# demoboard.net
KiCad netlist of a schematic drawn in Altium Designer
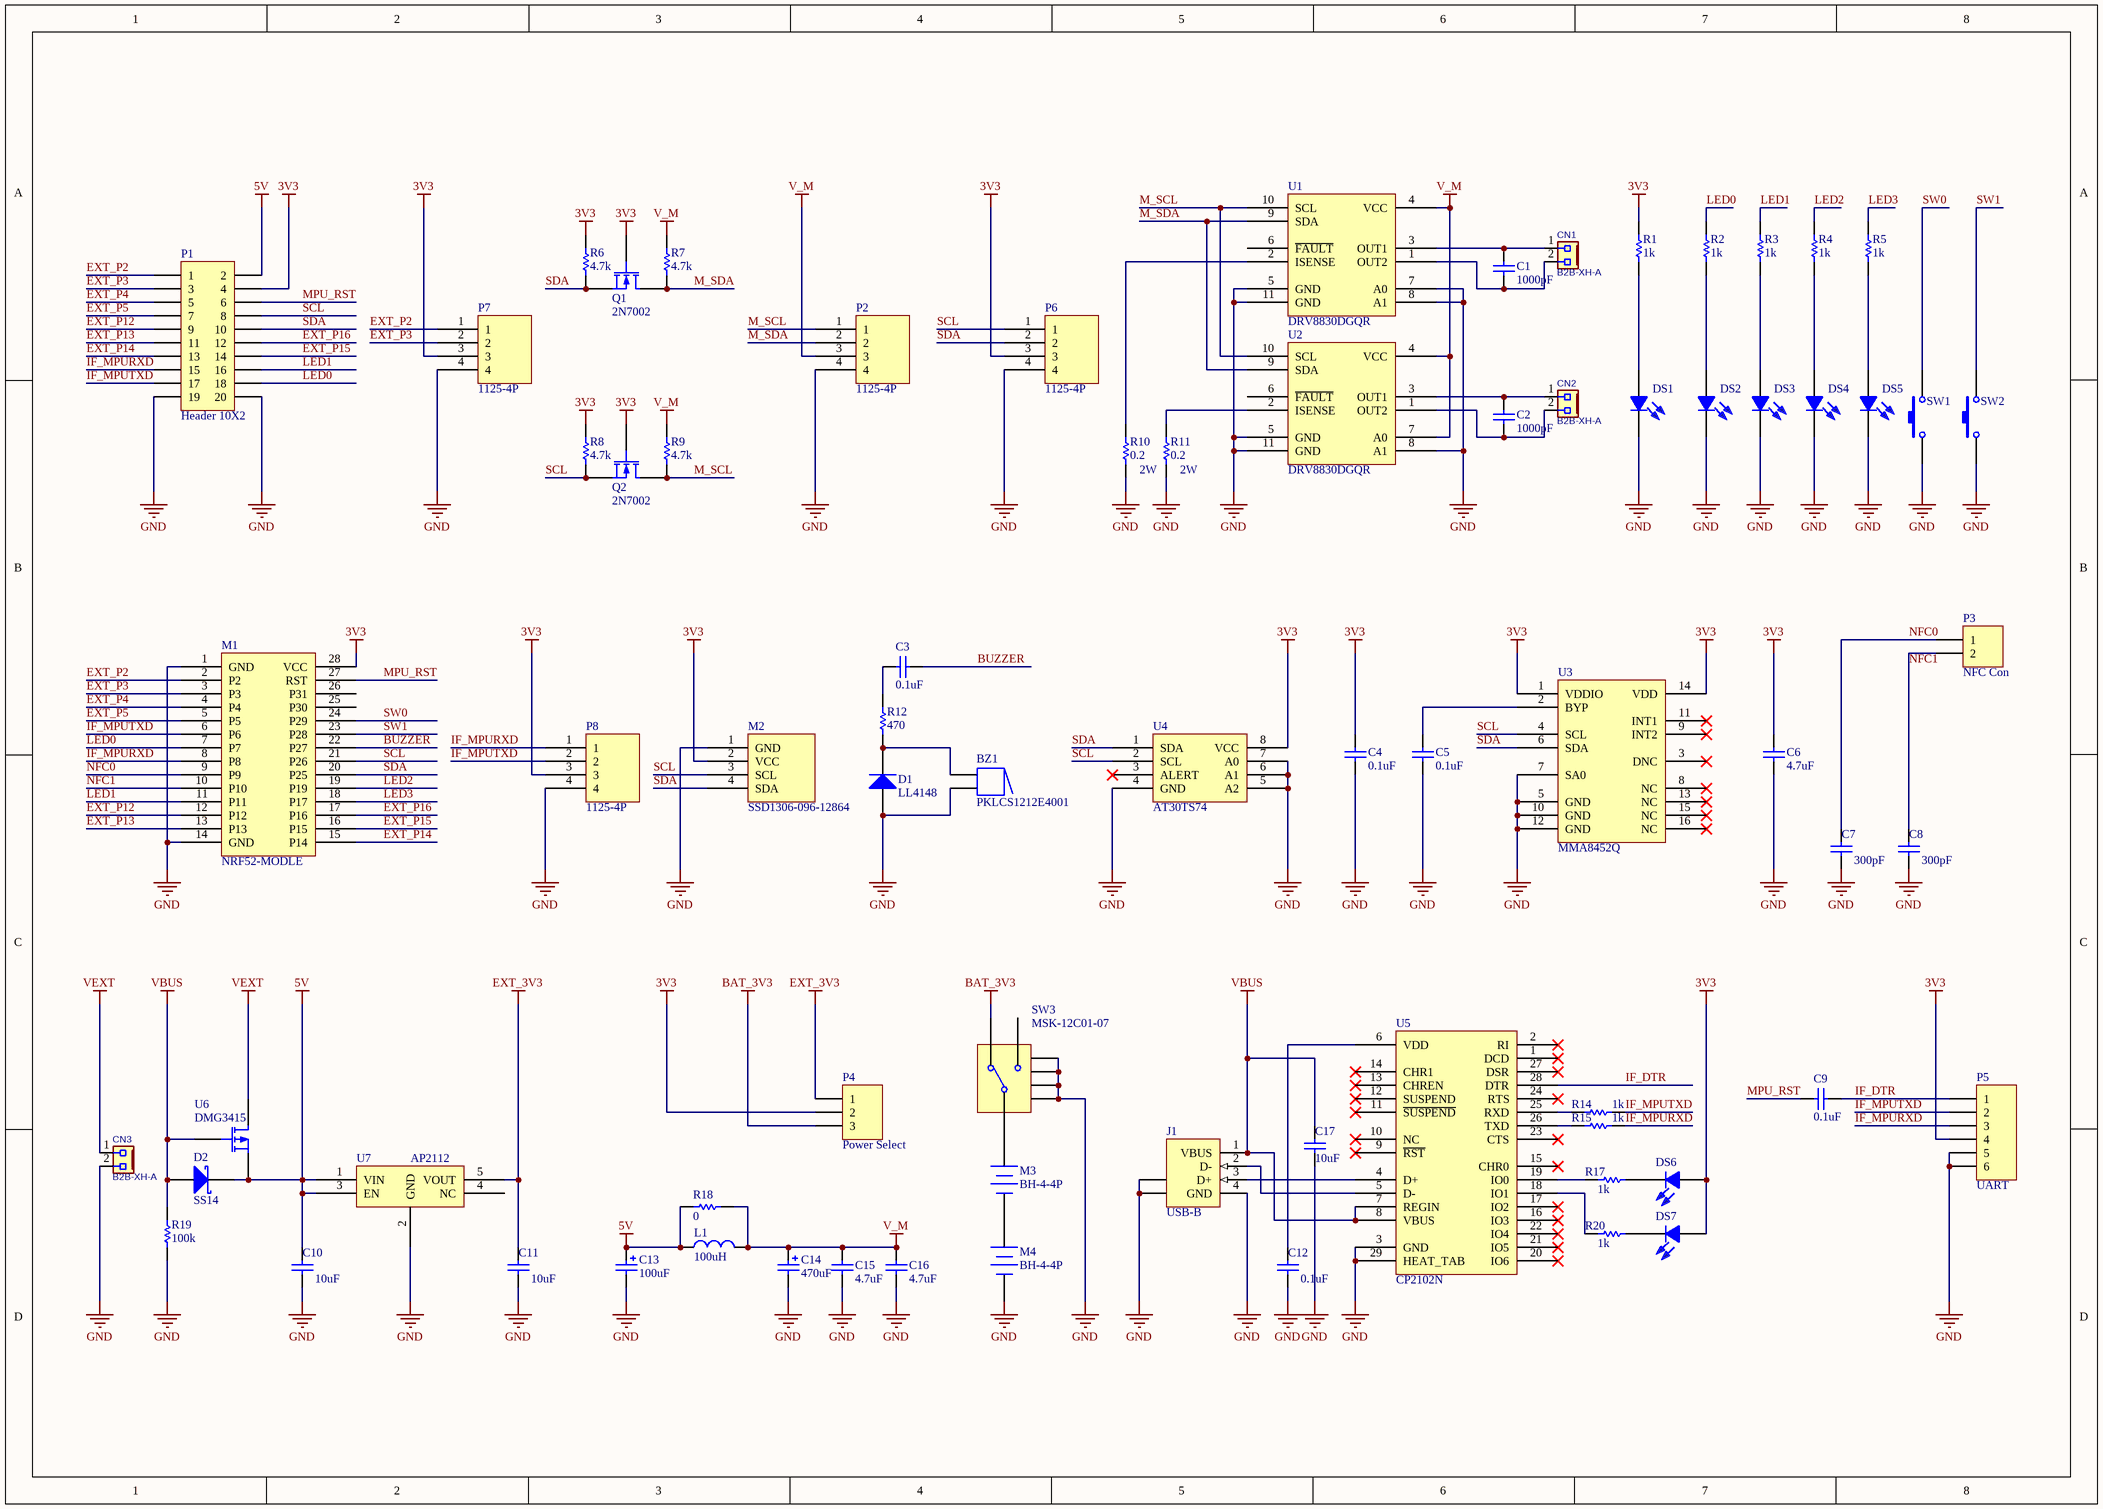
[diagram p0: demoboard.SchDoc]

(export (version "E")
  (design (tool "Eeschema 10.0.6"))
  (components
    (comp (ref "BZ1")
      (value "PKLCS1212E4001")
      (footprint "PKLCS1212E4001")
      (libsource (lib "newlib") (part "PKLCS1212E4001"))
    )
    (comp (ref "C1")
      (value "1000pF")
      (footprint "2012[0805]")
      (fields (field (name "Comment") "Cap1"))
      (libsource (lib "Other") (part "Cap1"))
    )
    (comp (ref "C2")
      (value "1000pF")
      (footprint "2012[0805]")
      (fields (field (name "Comment") "Cap1"))
      (libsource (lib "Other") (part "Cap1"))
    )
    (comp (ref "C3")
      (value "0.1uF")
      (footprint "2012[0805]")
      (fields (field (name "Comment") "Cap1"))
      (libsource (lib "Other") (part "Cap1"))
    )
    (comp (ref "C4")
      (value "0.1uF")
      (footprint "2012[0805]")
      (fields (field (name "Comment") "Cap1"))
      (libsource (lib "Other") (part "Cap1"))
    )
    (comp (ref "C5")
      (value "0.1uF")
      (footprint "2012[0805]")
      (fields (field (name "Comment") "Cap1"))
      (libsource (lib "Other") (part "Cap1"))
    )
    (comp (ref "C6")
      (value "4.7uF")
      (footprint "2012[0805]")
      (fields (field (name "Comment") "Cap1"))
      (libsource (lib "Other") (part "Cap1"))
    )
    (comp (ref "C7")
      (value "300pF")
      (footprint "2012[0805]")
      (fields (field (name "Comment") "Cap1"))
      (libsource (lib "Other") (part "Cap1"))
    )
    (comp (ref "C8")
      (value "300pF")
      (footprint "2012[0805]")
      (fields (field (name "Comment") "Cap1"))
      (libsource (lib "Other") (part "Cap1"))
    )
    (comp (ref "C9")
      (value "0.1uF")
      (footprint "2012[0805]")
      (fields (field (name "Comment") "Cap1"))
      (libsource (lib "Other") (part "Cap1"))
    )
    (comp (ref "C10")
      (value "10uF")
      (footprint "2012[0805]")
      (fields (field (name "Comment") "Cap1"))
      (libsource (lib "Other") (part "Cap1"))
    )
    (comp (ref "C11")
      (value "10uF")
      (footprint "2012[0805]")
      (fields (field (name "Comment") "Cap1"))
      (libsource (lib "Other") (part "Cap1"))
    )
    (comp (ref "C12")
      (value "0.1uF")
      (footprint "2012[0805]")
      (fields (field (name "Comment") "Cap1"))
      (libsource (lib "Other") (part "Cap1"))
    )
    (comp (ref "C13")
      (value "100uF")
      (footprint "CE04-8")
      (fields (field (name "Comment") "Cap2"))
      (libsource (lib "Other") (part "Cap2"))
    )
    (comp (ref "C14")
      (value "470uF")
      (footprint "CE04-8")
      (fields (field (name "Comment") "Cap2"))
      (libsource (lib "Other") (part "Cap2"))
    )
    (comp (ref "C15")
      (value "4.7uF")
      (footprint "2012[0805]")
      (fields (field (name "Comment") "Cap1"))
      (libsource (lib "Other") (part "Cap1"))
    )
    (comp (ref "C16")
      (value "4.7uF")
      (footprint "2012[0805]")
      (fields (field (name "Comment") "Cap1"))
      (libsource (lib "Other") (part "Cap1"))
    )
    (comp (ref "C17")
      (value "10uF")
      (footprint "2012[0805]")
      (fields (field (name "Comment") "Cap1"))
      (libsource (lib "Other") (part "Cap1"))
    )
    (comp (ref "CN1")
      (value "B2B-XH-A")
      (footprint "CND-B2B-XH-A")
      (description "XHシリーズ ベース付ポスト トップ型 2.5mmピッチ　250V 3A")
      (libsource (lib "Connector") (part "B2B-XH-A"))
    )
    (comp (ref "CN2")
      (value "B2B-XH-A")
      (footprint "CND-B2B-XH-A")
      (description "XHシリーズ ベース付ポスト トップ型 2.5mmピッチ　250V 3A")
      (libsource (lib "Connector") (part "B2B-XH-A"))
    )
    (comp (ref "CN3")
      (value "B2B-XH-A")
      (footprint "CND-B2B-XH-A")
      (description "XHシリーズ ベース付ポスト トップ型 2.5mmピッチ　250V 3A")
      (libsource (lib "Connector") (part "B2B-XH-A"))
    )
    (comp (ref "D1") (value "LL4148") (footprint "SOD80") (libsource (lib "Diode") (part "LL4148")))
    (comp (ref "D2") (value "SS14") (footprint "DO-214AC") (libsource (lib "Diode") (part "SS14")))
    (comp (ref "DS1") (value "~") (footprint "3216[1206]+A") (libsource (lib "Optical") (part "LED")))
    (comp (ref "DS2") (value "~") (footprint "3216[1206]+A") (libsource (lib "Optical") (part "LED")))
    (comp (ref "DS3") (value "~") (footprint "3216[1206]+A") (libsource (lib "Optical") (part "LED")))
    (comp (ref "DS4") (value "~") (footprint "3216[1206]+A") (libsource (lib "Optical") (part "LED")))
    (comp (ref "DS5") (value "~") (footprint "3216[1206]+A") (libsource (lib "Optical") (part "LED")))
    (comp (ref "DS6") (value "~") (footprint "3216[1206]+A") (libsource (lib "Optical") (part "LED")))
    (comp (ref "DS7") (value "~") (footprint "3216[1206]+A") (libsource (lib "Optical") (part "LED")))
    (comp (ref "J1")
      (value "USB-B")
      (footprint "USB-B-MICRO")
      (description "USB 1.1, Right Angle, Thru-Hole, B Type, Receptacle, 4 Position, White")
      (fields (field (name "PUBLISHER") "Altium Limited"))
      (libsource (lib "Connector") (part "USB-B"))
    )
    (comp (ref "L1")
      (value "100uH")
      (footprint "INDUCTOR-1212")
      (fields (field (name "Comment") "Inductor"))
      (libsource (lib "Other") (part "Inductor"))
    )
    (comp (ref "M1")
      (value "NRF52-MODLE")
      (footprint "NRF52-MODLE")
      (libsource (lib "newlib") (part "NRF52-MODLE"))
    )
    (comp (ref "M2")
      (value "SSD1306-096-12864")
      (footprint "SSD1306-096-12864")
      (libsource (lib "newlib") (part "SSD1306-096-12864"))
    )
    (comp (ref "M3") (value "BH-4-4P") (footprint "BH-4-4P") (libsource (lib "newlib") (part "BH-4-4P")))
    (comp (ref "M4") (value "BH-4-4P") (footprint "BH-4-4P") (libsource (lib "newlib") (part "BH-4-4P")))
    (comp (ref "P1")
      (value "Header 10X2")
      (footprint "HDR2X10")
      (description "Header, 10-Pin, Dual row")
      (fields (field (name "PUBLISHER") "Altium Limited"))
      (libsource (lib "Connector") (part "Header 10X2"))
    )
    (comp (ref "P2")
      (value "1125-4P")
      (footprint "1125-4P")
      (description "Seed Studio Grobe connector")
      (libsource (lib "newlib") (part "1125-4P"))
    )
    (comp (ref "P3")
      (value "NFC Con")
      (footprint "HDR1X2")
      (description "Header, 2-Pin")
      (fields (field (name "PUBLISHER") "Altium Limited"))
      (libsource (lib "Connector") (part "Header 2"))
    )
    (comp (ref "P4")
      (value "Power Select")
      (footprint "HDR1X3")
      (description "Header, 3-Pin")
      (fields (field (name "PUBLISHER") "Altium Limited"))
      (libsource (lib "Connector") (part "Header 3"))
    )
    (comp (ref "P5")
      (value "UART")
      (footprint "HDR1X6")
      (description "Header, 6-Pin")
      (fields (field (name "PUBLISHER") "Altium Limited"))
      (libsource (lib "Connector") (part "Header 6"))
    )
    (comp (ref "P6")
      (value "1125-4P")
      (footprint "1125-4P")
      (description "Seed Studio Grobe connector")
      (libsource (lib "newlib") (part "1125-4P"))
    )
    (comp (ref "P7")
      (value "1125-4P")
      (footprint "1125-4P")
      (description "Seed Studio Grobe connector")
      (libsource (lib "newlib") (part "1125-4P"))
    )
    (comp (ref "P8")
      (value "1125-4P")
      (footprint "1125-4P")
      (description "Seed Studio Grobe connector")
      (libsource (lib "newlib") (part "1125-4P"))
    )
    (comp (ref "Q1")
      (value "2N7002")
      (footprint "SOT23-3")
      (description "N-Channel MOSFET")
      (libsource (lib "Transistor") (part "2N7002"))
    )
    (comp (ref "Q2")
      (value "2N7002")
      (footprint "SOT23-3")
      (description "N-Channel MOSFET")
      (libsource (lib "Transistor") (part "2N7002"))
    )
    (comp (ref "R1")
      (value "1k")
      (footprint "2012[0805]")
      (fields (field (name "Comment") "Res"))
      (libsource (lib "Other") (part "Res"))
    )
    (comp (ref "R2")
      (value "1k")
      (footprint "2012[0805]")
      (fields (field (name "Comment") "Res"))
      (libsource (lib "Other") (part "Res"))
    )
    (comp (ref "R3")
      (value "1k")
      (footprint "2012[0805]")
      (fields (field (name "Comment") "Res"))
      (libsource (lib "Other") (part "Res"))
    )
    (comp (ref "R4")
      (value "1k")
      (footprint "2012[0805]")
      (fields (field (name "Comment") "Res"))
      (libsource (lib "Other") (part "Res"))
    )
    (comp (ref "R5")
      (value "1k")
      (footprint "2012[0805]")
      (fields (field (name "Comment") "Res"))
      (libsource (lib "Other") (part "Res"))
    )
    (comp (ref "R6")
      (value "4.7k")
      (footprint "2012[0805]")
      (fields (field (name "Comment") "Res"))
      (libsource (lib "Other") (part "Res"))
    )
    (comp (ref "R7")
      (value "4.7k")
      (footprint "2012[0805]")
      (fields (field (name "Comment") "Res"))
      (libsource (lib "Other") (part "Res"))
    )
    (comp (ref "R8")
      (value "4.7k")
      (footprint "2012[0805]")
      (fields (field (name "Comment") "Res"))
      (libsource (lib "Other") (part "Res"))
    )
    (comp (ref "R9")
      (value "4.7k")
      (footprint "2012[0805]")
      (fields (field (name "Comment") "Res"))
      (libsource (lib "Other") (part "Res"))
    )
    (comp (ref "R10")
      (value "0.2")
      (footprint "6332[2512]")
      (fields (field (name "ALTIUM_UNNAMED_1") "2W") (field (name "Comment") "Res"))
      (libsource (lib "Other") (part "Res"))
    )
    (comp (ref "R11")
      (value "0.2")
      (footprint "6332[2512]")
      (fields (field (name "ALTIUM_UNNAMED_1") "2W") (field (name "Comment") "Res"))
      (libsource (lib "Other") (part "Res"))
    )
    (comp (ref "R12")
      (value "470")
      (footprint "2012[0805]")
      (fields (field (name "Comment") "Res"))
      (libsource (lib "Other") (part "Res"))
    )
    (comp (ref "R14")
      (value "1k")
      (footprint "2012[0805]")
      (fields (field (name "Comment") "Res"))
      (libsource (lib "Other") (part "Res"))
    )
    (comp (ref "R15")
      (value "1k")
      (footprint "2012[0805]")
      (fields (field (name "Comment") "Res"))
      (libsource (lib "Other") (part "Res"))
    )
    (comp (ref "R17")
      (value "1k")
      (footprint "2012[0805]")
      (fields (field (name "Comment") "Res"))
      (libsource (lib "Other") (part "Res"))
    )
    (comp (ref "R18")
      (value "0")
      (footprint "2012[0805]")
      (fields (field (name "Comment") "Res"))
      (libsource (lib "Other") (part "Res"))
    )
    (comp (ref "R19")
      (value "100k")
      (footprint "2012[0805]")
      (fields (field (name "Comment") "Res"))
      (libsource (lib "Other") (part "Res"))
    )
    (comp (ref "R20")
      (value "1k")
      (footprint "2012[0805]")
      (fields (field (name "Comment") "Res"))
      (libsource (lib "Other") (part "Res"))
    )
    (comp (ref "SW1")
      (value "TL3342F160QG")
      (footprint "TL3342F160QG")
      (libsource (lib "Switch") (part "TL3342F160QG"))
    )
    (comp (ref "SW2")
      (value "TL3342F160QG")
      (footprint "TL3342F160QG")
      (libsource (lib "Switch") (part "TL3342F160QG"))
    )
    (comp (ref "SW3")
      (value "MSK-12C01-07")
      (footprint "MSK-12C01-07")
      (libsource (lib "Switch") (part "MSK-12C01-07"))
    )
    (comp (ref "U1")
      (value "DRV8830DGQR")
      (footprint "MSOP10TPH")
      (libsource (lib "newlib") (part "DRV8830DGQR"))
    )
    (comp (ref "U2")
      (value "DRV8830DGQR")
      (footprint "MSOP10TPH")
      (libsource (lib "newlib") (part "DRV8830DGQR"))
    )
    (comp (ref "U3")
      (value "MMA8452Q")
      (footprint "QFN16S-0.5")
      (description "MMA8452AQ")
      (libsource (lib "newlib") (part "MMA8452Q"))
    )
    (comp (ref "U4") (value "AT30TS74") (footprint "SOIC8") (libsource (lib "newlib") (part "AT30TS74")))
    (comp (ref "U5")
      (value "CP2102N")
      (footprint "QFN28-0.5")
      (fields (field (name "PART NUMBER") "CP2102"))
      (libsource (lib "newlib") (part "CP2102N"))
    )
    (comp (ref "U6")
      (value "DMG3415")
      (footprint "SOT23-3")
      (fields (field (name "PUBLISHER") "Altium Limited"))
      (libsource (lib "newlib") (part "DMG3415"))
    )
    (comp (ref "U7") (value "AP2112") (footprint "SOT23-5") (libsource (lib "newlib") (part "AP2112")))
  )
  (nets
    (net (code "1") (name "/BUZZER") (class "Default")
      (node (ref "C3") (pin "2") (pinfunction "2_2") (pintype "passive"))
      (node (ref "M1") (pin "22") (pinfunction "P27_22") (pintype "passive"))
    )
    (net (code "2") (name "/EXT_P2") (class "Default")
      (node (ref "M1") (pin "2") (pinfunction "P2_2") (pintype "passive"))
      (node (ref "P1") (pin "1") (pinfunction "1_1") (pintype "passive"))
      (node (ref "P7") (pin "1") (pinfunction "1_1") (pintype "passive"))
    )
    (net (code "3") (name "/EXT_P3") (class "Default")
      (node (ref "M1") (pin "3") (pinfunction "P3_3") (pintype "passive"))
      (node (ref "P1") (pin "3") (pinfunction "3_3") (pintype "passive"))
      (node (ref "P7") (pin "2") (pinfunction "2_2") (pintype "passive"))
    )
    (net (code "4") (name "/EXT_P4") (class "Default")
      (node (ref "M1") (pin "4") (pinfunction "P4_4") (pintype "passive"))
      (node (ref "P1") (pin "5") (pinfunction "5_5") (pintype "passive"))
    )
    (net (code "5") (name "/EXT_P5") (class "Default")
      (node (ref "M1") (pin "5") (pinfunction "P5_5") (pintype "passive"))
      (node (ref "P1") (pin "7") (pinfunction "7_7") (pintype "passive"))
    )
    (net (code "6") (name "/EXT_P12") (class "Default")
      (node (ref "M1") (pin "12") (pinfunction "P12_12") (pintype "passive"))
      (node (ref "P1") (pin "9") (pinfunction "9_9") (pintype "passive"))
    )
    (net (code "7") (name "/EXT_P13") (class "Default")
      (node (ref "M1") (pin "13") (pinfunction "P13_13") (pintype "passive"))
      (node (ref "P1") (pin "11") (pinfunction "11_11") (pintype "passive"))
    )
    (net (code "8") (name "/EXT_P14") (class "Default")
      (node (ref "M1") (pin "15") (pinfunction "P14_15") (pintype "passive"))
      (node (ref "P1") (pin "13") (pinfunction "13_13") (pintype "passive"))
    )
    (net (code "9") (name "/EXT_P15") (class "Default")
      (node (ref "M1") (pin "16") (pinfunction "P15_16") (pintype "passive"))
      (node (ref "P1") (pin "14") (pinfunction "14_14") (pintype "passive"))
    )
    (net (code "10") (name "/EXT_P16") (class "Default")
      (node (ref "M1") (pin "17") (pinfunction "P16_17") (pintype "passive"))
      (node (ref "P1") (pin "12") (pinfunction "12_12") (pintype "passive"))
    )
    (net (code "11") (name "/IF_DTR") (class "Default")
      (node (ref "C9") (pin "1") (pinfunction "1_1") (pintype "passive"))
      (node (ref "P5") (pin "1") (pinfunction "1_1") (pintype "passive"))
      (node (ref "U5") (pin "28") (pinfunction "DTR_28") (pintype "passive"))
    )
    (net (code "12") (name "/IF_MPURXD") (class "Default")
      (node (ref "M1") (pin "8") (pinfunction "P8_8") (pintype "passive"))
      (node (ref "P1") (pin "15") (pinfunction "15_15") (pintype "passive"))
      (node (ref "P5") (pin "3") (pinfunction "3_3") (pintype "passive"))
      (node (ref "P8") (pin "1") (pinfunction "1_1") (pintype "passive"))
      (node (ref "R15") (pin "2") (pinfunction "2_2") (pintype "passive"))
    )
    (net (code "13") (name "/IF_MPUTXD") (class "Default")
      (node (ref "M1") (pin "6") (pinfunction "P6_6") (pintype "passive"))
      (node (ref "P1") (pin "17") (pinfunction "17_17") (pintype "passive"))
      (node (ref "P5") (pin "2") (pinfunction "2_2") (pintype "passive"))
      (node (ref "P8") (pin "2") (pinfunction "2_2") (pintype "passive"))
      (node (ref "R14") (pin "2") (pinfunction "2_2") (pintype "passive"))
    )
    (net (code "14") (name "/LED0") (class "Default")
      (node (ref "M1") (pin "7") (pinfunction "P7_7") (pintype "passive"))
      (node (ref "P1") (pin "18") (pinfunction "18_18") (pintype "passive"))
      (node (ref "R2") (pin "1") (pinfunction "1_1") (pintype "passive"))
    )
    (net (code "15") (name "/LED1") (class "Default")
      (node (ref "M1") (pin "11") (pinfunction "P11_11") (pintype "passive"))
      (node (ref "P1") (pin "16") (pinfunction "16_16") (pintype "passive"))
      (node (ref "R3") (pin "1") (pinfunction "1_1") (pintype "passive"))
    )
    (net (code "16") (name "/LED2") (class "Default")
      (node (ref "M1") (pin "19") (pinfunction "P19_19") (pintype "passive"))
      (node (ref "R4") (pin "1") (pinfunction "1_1") (pintype "passive"))
    )
    (net (code "17") (name "/LED3") (class "Default")
      (node (ref "M1") (pin "18") (pinfunction "P17_18") (pintype "passive"))
      (node (ref "R5") (pin "1") (pinfunction "1_1") (pintype "passive"))
    )
    (net (code "18") (name "/MPU_RST") (class "Default")
      (node (ref "C9") (pin "2") (pinfunction "2_2") (pintype "passive"))
      (node (ref "M1") (pin "27") (pinfunction "RST_27") (pintype "passive"))
      (node (ref "P1") (pin "6") (pinfunction "6_6") (pintype "passive"))
    )
    (net (code "19") (name "/M_SCL") (class "Default")
      (node (ref "P2") (pin "1") (pinfunction "1_1") (pintype "passive"))
      (node (ref "Q2") (pin "3") (pinfunction "D_3") (pintype "passive"))
      (node (ref "R9") (pin "1") (pinfunction "1_1") (pintype "passive"))
      (node (ref "U1") (pin "10") (pinfunction "SCL_10") (pintype "passive"))
      (node (ref "U2") (pin "10") (pinfunction "SCL_10") (pintype "passive"))
    )
    (net (code "20") (name "/M_SDA") (class "Default")
      (node (ref "P2") (pin "2") (pinfunction "2_2") (pintype "passive"))
      (node (ref "Q1") (pin "3") (pinfunction "D_3") (pintype "passive"))
      (node (ref "R7") (pin "1") (pinfunction "1_1") (pintype "passive"))
      (node (ref "U1") (pin "9") (pinfunction "SDA_9") (pintype "passive"))
      (node (ref "U2") (pin "9") (pinfunction "SDA_9") (pintype "passive"))
    )
    (net (code "21") (name "/NFC0") (class "Default")
      (node (ref "C7") (pin "2") (pinfunction "2_2") (pintype "passive"))
      (node (ref "M1") (pin "9") (pinfunction "P9_9") (pintype "passive"))
      (node (ref "P3") (pin "1") (pinfunction "1_1") (pintype "passive"))
    )
    (net (code "22") (name "/NFC1") (class "Default")
      (node (ref "C8") (pin "2") (pinfunction "2_2") (pintype "passive"))
      (node (ref "M1") (pin "10") (pinfunction "P10_10") (pintype "passive"))
      (node (ref "P3") (pin "2") (pinfunction "2_2") (pintype "passive"))
    )
    (net (code "23") (name "/SCL") (class "Default")
      (node (ref "M1") (pin "21") (pinfunction "P26_21") (pintype "passive"))
      (node (ref "M2") (pin "3") (pinfunction "SCL_3") (pintype "passive"))
      (node (ref "P1") (pin "8") (pinfunction "8_8") (pintype "passive"))
      (node (ref "P6") (pin "1") (pinfunction "1_1") (pintype "passive"))
      (node (ref "Q2") (pin "2") (pinfunction "S_2") (pintype "passive"))
      (node (ref "R8") (pin "2") (pinfunction "2_2") (pintype "passive"))
      (node (ref "U3") (pin "4") (pinfunction "SCL_4") (pintype "passive"))
      (node (ref "U4") (pin "2") (pinfunction "SCL_2") (pintype "passive"))
    )
    (net (code "24") (name "/SDA") (class "Default")
      (node (ref "M1") (pin "20") (pinfunction "P25_20") (pintype "passive"))
      (node (ref "M2") (pin "4") (pinfunction "SDA_4") (pintype "passive"))
      (node (ref "P1") (pin "10") (pinfunction "10_10") (pintype "passive"))
      (node (ref "P6") (pin "2") (pinfunction "2_2") (pintype "passive"))
      (node (ref "Q1") (pin "2") (pinfunction "S_2") (pintype "passive"))
      (node (ref "R6") (pin "2") (pinfunction "2_2") (pintype "passive"))
      (node (ref "U3") (pin "6") (pinfunction "SDA_6") (pintype "passive"))
      (node (ref "U4") (pin "1") (pinfunction "SDA_1") (pintype "passive"))
    )
    (net (code "25") (name "/SW0") (class "Default")
      (node (ref "M1") (pin "24") (pinfunction "P29_24") (pintype "passive"))
      (node (ref "SW1") (pin "3") (pinfunction "3_3") (pintype "passive"))
    )
    (net (code "26") (name "/SW1") (class "Default")
      (node (ref "M1") (pin "23") (pinfunction "P28_23") (pintype "passive"))
      (node (ref "SW2") (pin "3") (pinfunction "3_3") (pintype "passive"))
    )
    (net (code "27") (name "3V3") (class "Default")
      (node (ref "C4") (pin "1") (pinfunction "1_1") (pintype "passive"))
      (node (ref "C6") (pin "1") (pinfunction "1_1") (pintype "passive"))
      (node (ref "DS6") (pin "1") (pintype "passive"))
      (node (ref "DS7") (pin "1") (pintype "passive"))
      (node (ref "M1") (pin "28") (pinfunction "VCC_28") (pintype "passive"))
      (node (ref "M2") (pin "2") (pinfunction "VCC_2") (pintype "passive"))
      (node (ref "P1") (pin "4") (pinfunction "4_4") (pintype "passive"))
      (node (ref "P4") (pin "2") (pinfunction "2_2") (pintype "passive"))
      (node (ref "P5") (pin "4") (pinfunction "4_4") (pintype "passive"))
      (node (ref "P6") (pin "3") (pinfunction "3_3") (pintype "passive"))
      (node (ref "P7") (pin "3") (pinfunction "3_3") (pintype "passive"))
      (node (ref "P8") (pin "3") (pinfunction "3_3") (pintype "passive"))
      (node (ref "Q1") (pin "1") (pinfunction "G_1") (pintype "passive"))
      (node (ref "Q2") (pin "1") (pinfunction "G_1") (pintype "passive"))
      (node (ref "R1") (pin "1") (pinfunction "1_1") (pintype "passive"))
      (node (ref "R6") (pin "1") (pinfunction "1_1") (pintype "passive"))
      (node (ref "R8") (pin "1") (pinfunction "1_1") (pintype "passive"))
      (node (ref "U3") (pin "1") (pinfunction "VDDIO_1") (pintype "passive"))
      (node (ref "U3") (pin "14") (pinfunction "VDD_14") (pintype "passive"))
      (node (ref "U4") (pin "8") (pinfunction "VCC_8") (pintype "passive"))
    )
    (net (code "28") (name "5V") (class "Default")
      (node (ref "C10") (pin "2") (pinfunction "2_2") (pintype "passive"))
      (node (ref "C13") (pin "1") (pinfunction "1_1") (pintype "passive"))
      (node (ref "D2") (pin "2") (pinfunction "K_2") (pintype "passive"))
      (node (ref "L1") (pin "1") (pinfunction "1_1") (pintype "passive"))
      (node (ref "P1") (pin "2") (pinfunction "2_2") (pintype "passive"))
      (node (ref "R18") (pin "1") (pinfunction "1_1") (pintype "passive"))
      (node (ref "U6") (pin "2") (pinfunction "S_2") (pintype "passive"))
      (node (ref "U7") (pin "1") (pinfunction "VIN_1") (pintype "passive"))
      (node (ref "U7") (pin "3") (pinfunction "EN_3") (pintype "passive"))
    )
    (net (code "29") (name "BAT_3V3") (class "Default")
      (node (ref "P4") (pin "3") (pinfunction "3_3") (pintype "passive"))
      (node (ref "SW3") (pin "1") (pinfunction "1_1") (pintype "passive"))
    )
    (net (code "30") (name "EXT_3V3") (class "Default")
      (node (ref "C11") (pin "2") (pinfunction "2_2") (pintype "passive"))
      (node (ref "P4") (pin "1") (pinfunction "1_1") (pintype "passive"))
      (node (ref "U7") (pin "5") (pinfunction "VOUT_5") (pintype "passive"))
    )
    (net (code "31") (name "GND") (class "Default")
      (node (ref "BZ1") (pin "2") (pinfunction "2_2") (pintype "passive"))
      (node (ref "C10") (pin "1") (pinfunction "1_1") (pintype "passive"))
      (node (ref "C11") (pin "1") (pinfunction "1_1") (pintype "passive"))
      (node (ref "C12") (pin "1") (pinfunction "1_1") (pintype "passive"))
      (node (ref "C13") (pin "2") (pinfunction "2_2") (pintype "passive"))
      (node (ref "C14") (pin "2") (pinfunction "2_2") (pintype "passive"))
      (node (ref "C15") (pin "2") (pinfunction "2_2") (pintype "passive"))
      (node (ref "C16") (pin "2") (pinfunction "2_2") (pintype "passive"))
      (node (ref "C17") (pin "1") (pinfunction "1_1") (pintype "passive"))
      (node (ref "C4") (pin "2") (pinfunction "2_2") (pintype "passive"))
      (node (ref "C5") (pin "2") (pinfunction "2_2") (pintype "passive"))
      (node (ref "C6") (pin "2") (pinfunction "2_2") (pintype "passive"))
      (node (ref "C7") (pin "1") (pinfunction "1_1") (pintype "passive"))
      (node (ref "C8") (pin "1") (pinfunction "1_1") (pintype "passive"))
      (node (ref "CN3") (pin "2") (pinfunction "2_2") (pintype "passive"))
      (node (ref "D1") (pin "1") (pinfunction "A_1") (pintype "passive"))
      (node (ref "DS1") (pin "2") (pintype "passive"))
      (node (ref "DS2") (pin "2") (pintype "passive"))
      (node (ref "DS3") (pin "2") (pintype "passive"))
      (node (ref "DS4") (pin "2") (pintype "passive"))
      (node (ref "DS5") (pin "2") (pintype "passive"))
      (node (ref "J1") (pin "4") (pinfunction "GND_4") (pintype "power_in"))
      (node (ref "J1") (pin "5") (pinfunction "SHLD_5") (pintype "passive"))
      (node (ref "J1") (pin "6") (pinfunction "SHLD_6") (pintype "passive"))
      (node (ref "M1") (pin "1") (pinfunction "GND_1") (pintype "passive"))
      (node (ref "M1") (pin "14") (pinfunction "GND_14") (pintype "passive"))
      (node (ref "M2") (pin "1") (pinfunction "GND_1") (pintype "passive"))
      (node (ref "M4") (pin "2") (pinfunction "-_2") (pintype "passive"))
      (node (ref "P1") (pin "19") (pinfunction "19_19") (pintype "passive"))
      (node (ref "P1") (pin "20") (pinfunction "20_20") (pintype "passive"))
      (node (ref "P2") (pin "4") (pinfunction "4_4") (pintype "passive"))
      (node (ref "P5") (pin "5") (pinfunction "5_5") (pintype "passive"))
      (node (ref "P5") (pin "6") (pinfunction "6_6") (pintype "passive"))
      (node (ref "P6") (pin "4") (pinfunction "4_4") (pintype "passive"))
      (node (ref "P7") (pin "4") (pinfunction "4_4") (pintype "passive"))
      (node (ref "P8") (pin "4") (pinfunction "4_4") (pintype "passive"))
      (node (ref "R10") (pin "1") (pinfunction "1_1") (pintype "passive"))
      (node (ref "R11") (pin "1") (pinfunction "1_1") (pintype "passive"))
      (node (ref "R19") (pin "1") (pinfunction "1_1") (pintype "passive"))
      (node (ref "SW1") (pin "1") (pinfunction "1_1") (pintype "passive"))
      (node (ref "SW2") (pin "1") (pinfunction "1_1") (pintype "passive"))
      (node (ref "SW3") (pin "4") (pinfunction "4_4") (pintype "passive"))
      (node (ref "SW3") (pin "5") (pinfunction "5_5") (pintype "passive"))
      (node (ref "SW3") (pin "6") (pinfunction "6_6") (pintype "passive"))
      (node (ref "SW3") (pin "7") (pinfunction "7_7") (pintype "passive"))
      (node (ref "U1") (pin "11") (pinfunction "GND_11") (pintype "passive"))
      (node (ref "U1") (pin "5") (pinfunction "GND_5") (pintype "passive"))
      (node (ref "U1") (pin "7") (pinfunction "A0_7") (pintype "passive"))
      (node (ref "U1") (pin "8") (pinfunction "A1_8") (pintype "passive"))
      (node (ref "U2") (pin "11") (pinfunction "GND_11") (pintype "passive"))
      (node (ref "U2") (pin "5") (pinfunction "GND_5") (pintype "passive"))
      (node (ref "U2") (pin "8") (pinfunction "A1_8") (pintype "passive"))
      (node (ref "U3") (pin "10") (pinfunction "GND_10") (pintype "passive"))
      (node (ref "U3") (pin "12") (pinfunction "GND_12") (pintype "passive"))
      (node (ref "U3") (pin "5") (pinfunction "GND_5") (pintype "passive"))
      (node (ref "U3") (pin "7") (pinfunction "SA0_7") (pintype "passive"))
      (node (ref "U4") (pin "4") (pinfunction "GND_4") (pintype "passive"))
      (node (ref "U4") (pin "5") (pinfunction "A2_5") (pintype "passive"))
      (node (ref "U4") (pin "6") (pinfunction "A1_6") (pintype "passive"))
      (node (ref "U4") (pin "7") (pinfunction "A0_7") (pintype "passive"))
      (node (ref "U5") (pin "29") (pinfunction "HEAT_TAB_29") (pintype "passive"))
      (node (ref "U5") (pin "3") (pinfunction "GND_3") (pintype "passive"))
      (node (ref "U7") (pin "2") (pinfunction "GND_2") (pintype "passive"))
    )
    (net (code "32") (name "Net-(C3-Pad1)") (class "Default")
      (node (ref "C3") (pin "1") (pinfunction "1_1") (pintype "passive"))
      (node (ref "R12") (pin "2") (pinfunction "2_2") (pintype "passive"))
    )
    (net (code "33") (name "Net-(D1-K)") (class "Default")
      (node (ref "BZ1") (pin "1") (pinfunction "1_1") (pintype "passive"))
      (node (ref "D1") (pin "2") (pinfunction "K_2") (pintype "passive"))
      (node (ref "R12") (pin "1") (pinfunction "1_1") (pintype "passive"))
    )
    (net (code "34") (name "Net-(DS1-Pad1)") (class "Default")
      (node (ref "DS1") (pin "1") (pintype "passive"))
      (node (ref "R1") (pin "2") (pinfunction "2_2") (pintype "passive"))
    )
    (net (code "35") (name "Net-(DS2-Pad1)") (class "Default")
      (node (ref "DS2") (pin "1") (pintype "passive"))
      (node (ref "R2") (pin "2") (pinfunction "2_2") (pintype "passive"))
    )
    (net (code "36") (name "Net-(DS3-Pad1)") (class "Default")
      (node (ref "DS3") (pin "1") (pintype "passive"))
      (node (ref "R3") (pin "2") (pinfunction "2_2") (pintype "passive"))
    )
    (net (code "37") (name "Net-(DS4-Pad1)") (class "Default")
      (node (ref "DS4") (pin "1") (pintype "passive"))
      (node (ref "R4") (pin "2") (pinfunction "2_2") (pintype "passive"))
    )
    (net (code "38") (name "Net-(DS5-Pad1)") (class "Default")
      (node (ref "DS5") (pin "1") (pintype "passive"))
      (node (ref "R5") (pin "2") (pinfunction "2_2") (pintype "passive"))
    )
    (net (code "39") (name "Net-(DS6-Pad2)") (class "Default")
      (node (ref "DS6") (pin "2") (pintype "passive"))
      (node (ref "R17") (pin "1") (pinfunction "1_1") (pintype "passive"))
    )
    (net (code "40") (name "Net-(DS7-Pad2)") (class "Default")
      (node (ref "DS7") (pin "2") (pintype "passive"))
      (node (ref "R20") (pin "1") (pinfunction "1_1") (pintype "passive"))
    )
    (net (code "41") (name "Net-(J1-D+)") (class "Default")
      (node (ref "J1") (pin "3") (pinfunction "D+_3") (pintype "input"))
      (node (ref "U5") (pin "4") (pinfunction "D+_4") (pintype "passive"))
    )
    (net (code "42") (name "Net-(J1-D-)") (class "Default")
      (node (ref "J1") (pin "2") (pinfunction "D-_2") (pintype "input"))
      (node (ref "U5") (pin "5") (pinfunction "D-_5") (pintype "passive"))
    )
    (net (code "43") (name "Net-(M3-+)") (class "Default")
      (node (ref "M3") (pin "1") (pinfunction "+_1") (pintype "passive"))
      (node (ref "SW3") (pin "2") (pinfunction "2_2") (pintype "passive"))
    )
    (net (code "44") (name "Net-(M3--)") (class "Default")
      (node (ref "M3") (pin "2") (pinfunction "-_2") (pintype "passive"))
      (node (ref "M4") (pin "1") (pinfunction "+_1") (pintype "passive"))
    )
    (net (code "45") (name "Net-(U1-ISENSE)") (class "Default")
      (node (ref "R10") (pin "2") (pinfunction "2_2") (pintype "passive"))
      (node (ref "U1") (pin "2") (pinfunction "ISENSE_2") (pintype "passive"))
    )
    (net (code "46") (name "Net-(U1-OUT1)") (class "Default")
      (node (ref "C1") (pin "1") (pinfunction "1_1") (pintype "passive"))
      (node (ref "CN1") (pin "1") (pinfunction "1_1") (pintype "passive"))
      (node (ref "U1") (pin "3") (pinfunction "OUT1_3") (pintype "passive"))
    )
    (net (code "47") (name "Net-(U1-OUT2)") (class "Default")
      (node (ref "C1") (pin "2") (pinfunction "2_2") (pintype "passive"))
      (node (ref "CN1") (pin "2") (pinfunction "2_2") (pintype "passive"))
      (node (ref "U1") (pin "1") (pinfunction "OUT2_1") (pintype "passive"))
    )
    (net (code "48") (name "Net-(U2-ISENSE)") (class "Default")
      (node (ref "R11") (pin "2") (pinfunction "2_2") (pintype "passive"))
      (node (ref "U2") (pin "2") (pinfunction "ISENSE_2") (pintype "passive"))
    )
    (net (code "49") (name "Net-(U2-OUT1)") (class "Default")
      (node (ref "C2") (pin "1") (pinfunction "1_1") (pintype "passive"))
      (node (ref "CN2") (pin "1") (pinfunction "1_1") (pintype "passive"))
      (node (ref "U2") (pin "3") (pinfunction "OUT1_3") (pintype "passive"))
    )
    (net (code "50") (name "Net-(U2-OUT2)") (class "Default")
      (node (ref "C2") (pin "2") (pinfunction "2_2") (pintype "passive"))
      (node (ref "CN2") (pin "2") (pinfunction "2_2") (pintype "passive"))
      (node (ref "U2") (pin "1") (pinfunction "OUT2_1") (pintype "passive"))
    )
    (net (code "51") (name "Net-(U3-BYP)") (class "Default")
      (node (ref "C5") (pin "1") (pinfunction "1_1") (pintype "passive"))
      (node (ref "U3") (pin "2") (pinfunction "BYP_2") (pintype "passive"))
    )
    (net (code "52") (name "Net-(U5-IO0)") (class "Default")
      (node (ref "R17") (pin "2") (pinfunction "2_2") (pintype "passive"))
      (node (ref "U5") (pin "19") (pinfunction "IO0_19") (pintype "passive"))
    )
    (net (code "53") (name "Net-(U5-IO1)") (class "Default")
      (node (ref "R20") (pin "2") (pinfunction "2_2") (pintype "passive"))
      (node (ref "U5") (pin "18") (pinfunction "IO1_18") (pintype "passive"))
    )
    (net (code "54") (name "Net-(U5-RXD)") (class "Default")
      (node (ref "R14") (pin "1") (pinfunction "1_1") (pintype "passive"))
      (node (ref "U5") (pin "25") (pinfunction "RXD_25") (pintype "passive"))
    )
    (net (code "55") (name "Net-(U5-TXD)") (class "Default")
      (node (ref "R15") (pin "1") (pinfunction "1_1") (pintype "passive"))
      (node (ref "U5") (pin "26") (pinfunction "TXD_26") (pintype "passive"))
    )
    (net (code "56") (name "Net-(U5-VDD)") (class "Default")
      (node (ref "C12") (pin "2") (pinfunction "2_2") (pintype "passive"))
      (node (ref "U5") (pin "6") (pinfunction "VDD_6") (pintype "passive"))
    )
    (net (code "57") (name "VBUS") (class "Default")
      (node (ref "C17") (pin "2") (pinfunction "2_2") (pintype "passive"))
      (node (ref "D2") (pin "1") (pinfunction "A_1") (pintype "passive"))
      (node (ref "J1") (pin "1") (pinfunction "VBUS_1") (pintype "power_in"))
      (node (ref "R19") (pin "2") (pinfunction "2_2") (pintype "passive"))
      (node (ref "U5") (pin "7") (pinfunction "REGIN_7") (pintype "passive"))
      (node (ref "U5") (pin "8") (pinfunction "VBUS_8") (pintype "passive"))
      (node (ref "U6") (pin "1") (pinfunction "G_1") (pintype "passive"))
    )
    (net (code "58") (name "VEXT") (class "Default")
      (node (ref "CN3") (pin "1") (pinfunction "1_1") (pintype "passive"))
      (node (ref "U6") (pin "3") (pinfunction "D_3") (pintype "passive"))
    )
    (net (code "59") (name "V_M") (class "Default")
      (node (ref "C14") (pin "1") (pinfunction "1_1") (pintype "passive"))
      (node (ref "C15") (pin "1") (pinfunction "1_1") (pintype "passive"))
      (node (ref "C16") (pin "1") (pinfunction "1_1") (pintype "passive"))
      (node (ref "L1") (pin "2") (pinfunction "2_2") (pintype "passive"))
      (node (ref "P2") (pin "3") (pinfunction "3_3") (pintype "passive"))
      (node (ref "R18") (pin "2") (pinfunction "2_2") (pintype "passive"))
      (node (ref "R7") (pin "2") (pinfunction "2_2") (pintype "passive"))
      (node (ref "R9") (pin "2") (pinfunction "2_2") (pintype "passive"))
      (node (ref "U1") (pin "4") (pinfunction "VCC_4") (pintype "passive"))
      (node (ref "U2") (pin "4") (pinfunction "VCC_4") (pintype "passive"))
      (node (ref "U2") (pin "7") (pinfunction "A0_7") (pintype "passive"))
    )
    (net (code "60") (name "unconnected-(M1-P30-Pad25)") (class "Default")
      (node (ref "M1") (pin "25") (pinfunction "P30_25") (pintype "passive"))
    )
    (net (code "61") (name "unconnected-(M1-P31-Pad26)") (class "Default")
      (node (ref "M1") (pin "26") (pinfunction "P31_26") (pintype "passive"))
    )
    (net (code "62") (name "unconnected-(SW3-Pad3)") (class "Default")
      (node (ref "SW3") (pin "3") (pinfunction "3_3") (pintype "passive"))
    )
    (net (code "63") (name "unconnected-(U1-~{FAULT}-Pad6)") (class "Default")
      (node (ref "U1") (pin "6") (pinfunction "~{FAULT}_6") (pintype "passive"))
    )
    (net (code "64") (name "unconnected-(U2-~{FAULT}-Pad6)") (class "Default")
      (node (ref "U2") (pin "6") (pinfunction "~{FAULT}_6") (pintype "passive"))
    )
    (net (code "65") (name "unconnected-(U3-DNC-Pad3)") (class "Default")
      (node (ref "U3") (pin "3") (pinfunction "DNC_3") (pintype "passive+no_connect"))
    )
    (net (code "66") (name "unconnected-(U3-INT1-Pad11)") (class "Default")
      (node (ref "U3") (pin "11") (pinfunction "INT1_11") (pintype "passive+no_connect"))
    )
    (net (code "67") (name "unconnected-(U3-INT2-Pad9)") (class "Default")
      (node (ref "U3") (pin "9") (pinfunction "INT2_9") (pintype "passive+no_connect"))
    )
    (net (code "68") (name "unconnected-(U3-NC-Pad8)") (class "Default")
      (node (ref "U3") (pin "8") (pinfunction "NC_8") (pintype "passive+no_connect"))
    )
    (net (code "69") (name "unconnected-(U3-NC-Pad13)") (class "Default")
      (node (ref "U3") (pin "13") (pinfunction "NC_13") (pintype "passive+no_connect"))
    )
    (net (code "70") (name "unconnected-(U3-NC-Pad15)") (class "Default")
      (node (ref "U3") (pin "15") (pinfunction "NC_15") (pintype "passive+no_connect"))
    )
    (net (code "71") (name "unconnected-(U3-NC-Pad16)") (class "Default")
      (node (ref "U3") (pin "16") (pinfunction "NC_16") (pintype "passive+no_connect"))
    )
    (net (code "72") (name "unconnected-(U4-ALERT-Pad3)") (class "Default")
      (node (ref "U4") (pin "3") (pinfunction "ALERT_3") (pintype "passive+no_connect"))
    )
    (net (code "73") (name "unconnected-(U5-CHR0-Pad15)") (class "Default")
      (node (ref "U5") (pin "15") (pinfunction "CHR0_15") (pintype "passive+no_connect"))
    )
    (net (code "74") (name "unconnected-(U5-CHR1-Pad14)") (class "Default")
      (node (ref "U5") (pin "14") (pinfunction "CHR1_14") (pintype "passive+no_connect"))
    )
    (net (code "75") (name "unconnected-(U5-CHREN-Pad13)") (class "Default")
      (node (ref "U5") (pin "13") (pinfunction "CHREN_13") (pintype "passive+no_connect"))
    )
    (net (code "76") (name "unconnected-(U5-CTS-Pad23)") (class "Default")
      (node (ref "U5") (pin "23") (pinfunction "CTS_23") (pintype "passive+no_connect"))
    )
    (net (code "77") (name "unconnected-(U5-DCD-Pad1)") (class "Default")
      (node (ref "U5") (pin "1") (pinfunction "DCD_1") (pintype "passive+no_connect"))
    )
    (net (code "78") (name "unconnected-(U5-DSR-Pad27)") (class "Default")
      (node (ref "U5") (pin "27") (pinfunction "DSR_27") (pintype "passive+no_connect"))
    )
    (net (code "79") (name "unconnected-(U5-IO2-Pad17)") (class "Default")
      (node (ref "U5") (pin "17") (pinfunction "IO2_17") (pintype "passive+no_connect"))
    )
    (net (code "80") (name "unconnected-(U5-IO3-Pad16)") (class "Default")
      (node (ref "U5") (pin "16") (pinfunction "IO3_16") (pintype "passive+no_connect"))
    )
    (net (code "81") (name "unconnected-(U5-IO4-Pad22)") (class "Default")
      (node (ref "U5") (pin "22") (pinfunction "IO4_22") (pintype "passive+no_connect"))
    )
    (net (code "82") (name "unconnected-(U5-IO5-Pad21)") (class "Default")
      (node (ref "U5") (pin "21") (pinfunction "IO5_21") (pintype "passive+no_connect"))
    )
    (net (code "83") (name "unconnected-(U5-IO6-Pad20)") (class "Default")
      (node (ref "U5") (pin "20") (pinfunction "IO6_20") (pintype "passive+no_connect"))
    )
    (net (code "84") (name "unconnected-(U5-NC-Pad10)") (class "Default")
      (node (ref "U5") (pin "10") (pinfunction "NC_10") (pintype "passive+no_connect"))
    )
    (net (code "85") (name "unconnected-(U5-RI-Pad2)") (class "Default")
      (node (ref "U5") (pin "2") (pinfunction "RI_2") (pintype "passive+no_connect"))
    )
    (net (code "86") (name "unconnected-(U5-RTS-Pad24)") (class "Default")
      (node (ref "U5") (pin "24") (pinfunction "RTS_24") (pintype "passive+no_connect"))
    )
    (net (code "87") (name "unconnected-(U5-SUSPEND-Pad12)") (class "Default")
      (node (ref "U5") (pin "12") (pinfunction "SUSPEND_12") (pintype "passive+no_connect"))
    )
    (net (code "88") (name "unconnected-(U5-~{RST}-Pad9)") (class "Default")
      (node (ref "U5") (pin "9") (pinfunction "~{RST}_9") (pintype "passive+no_connect"))
    )
    (net (code "89") (name "unconnected-(U5-~{SUSPEND}-Pad11)") (class "Default")
      (node (ref "U5") (pin "11") (pinfunction "~{SUSPEND}_11") (pintype "passive+no_connect"))
    )
    (net (code "90") (name "unconnected-(U7-NC-Pad4)") (class "Default")
      (node (ref "U7") (pin "4") (pinfunction "NC_4") (pintype "passive"))
    )
  )
)
